# Fall_17_Workshop_Schem.net
KiCad netlist of a schematic drawn in EAGLE
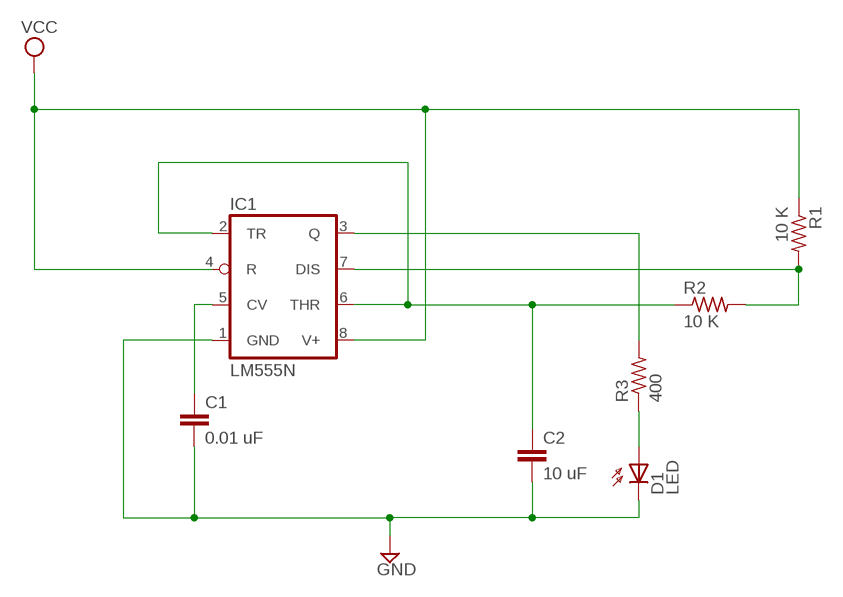
[diagram p0: schematic, sheet 1]

(export (version "E")
  (design (tool "Eeschema 10.0.6"))
  (components
    (comp (ref "C1")
      (value "0.01 uF")
      (footprint "eagle-import:C5B2.5")
      (libsource (lib "eagle-import") (part "C5/2.5"))
    )
    (comp (ref "C2")
      (value "10 uF")
      (footprint "eagle-import:C5B2.5")
      (libsource (lib "eagle-import") (part "C5/2.5"))
    )
    (comp (ref "D1")
      (value "LED")
      (footprint "eagle-import:SFH205")
      (libsource (lib "eagle-import") (part "SFH205"))
    )
    (comp (ref "IC1")
      (value "LM555N")
      (footprint "eagle-import:DIL08")
      (libsource (lib "eagle-import") (part "555NLM"))
    )
    (comp (ref "R1")
      (value "10 K")
      (footprint "eagle-import:0204_7")
      (libsource (lib "eagle-import") (part "R-US_0204/7"))
    )
    (comp (ref "R2")
      (value "10 K")
      (footprint "eagle-import:0204_7")
      (libsource (lib "eagle-import") (part "R-US_0204/7"))
    )
    (comp (ref "R3")
      (value "400")
      (footprint "eagle-import:0204_7")
      (libsource (lib "eagle-import") (part "R-US_0204/7"))
    )
  )
  (nets
    (net (code "1") (name "GND") (class "Default")
      (node (ref "C1") (pin "2") (pinfunction "2_2") (pintype "passive"))
      (node (ref "C2") (pin "2") (pinfunction "2_2") (pintype "passive"))
      (node (ref "D1") (pin "K") (pinfunction "C_K") (pintype "passive"))
      (node (ref "IC1") (pin "1") (pinfunction "GND_1") (pintype "power_in"))
    )
    (net (code "2") (name "Net-(D1-PadA)") (class "Default")
      (node (ref "D1") (pin "A") (pinfunction "A_A") (pintype "passive"))
      (node (ref "R3") (pin "1") (pinfunction "1_1") (pintype "passive"))
    )
    (net (code "3") (name "Net-(IC1-CV)") (class "Default")
      (node (ref "C1") (pin "1") (pinfunction "1_1") (pintype "passive"))
      (node (ref "IC1") (pin "5") (pinfunction "CV_5") (pintype "input"))
    )
    (net (code "4") (name "Net-(IC1-DIS)") (class "Default")
      (node (ref "IC1") (pin "7") (pinfunction "DIS_7") (pintype "input"))
      (node (ref "R1") (pin "2") (pinfunction "2_2") (pintype "passive"))
      (node (ref "R2") (pin "2") (pinfunction "2_2") (pintype "passive"))
    )
    (net (code "5") (name "Net-(IC1-Q)") (class "Default")
      (node (ref "IC1") (pin "3") (pinfunction "Q_3") (pintype "output"))
      (node (ref "R3") (pin "2") (pinfunction "2_2") (pintype "passive"))
    )
    (net (code "6") (name "Net-(IC1-THR)") (class "Default")
      (node (ref "C2") (pin "1") (pinfunction "1_1") (pintype "passive"))
      (node (ref "IC1") (pin "2") (pinfunction "TR_2") (pintype "input"))
      (node (ref "IC1") (pin "6") (pinfunction "THR_6") (pintype "input"))
      (node (ref "R2") (pin "1") (pinfunction "1_1") (pintype "passive"))
    )
    (net (code "7") (name "VCC") (class "Default")
      (node (ref "IC1") (pin "4") (pinfunction "R_4") (pintype "input"))
      (node (ref "IC1") (pin "8") (pinfunction "V+_8") (pintype "power_in"))
      (node (ref "R1") (pin "1") (pinfunction "1_1") (pintype "passive"))
    )
  )
)
